# Servo-Power.net
KiCad netlist of a schematic drawn in Altium Designer
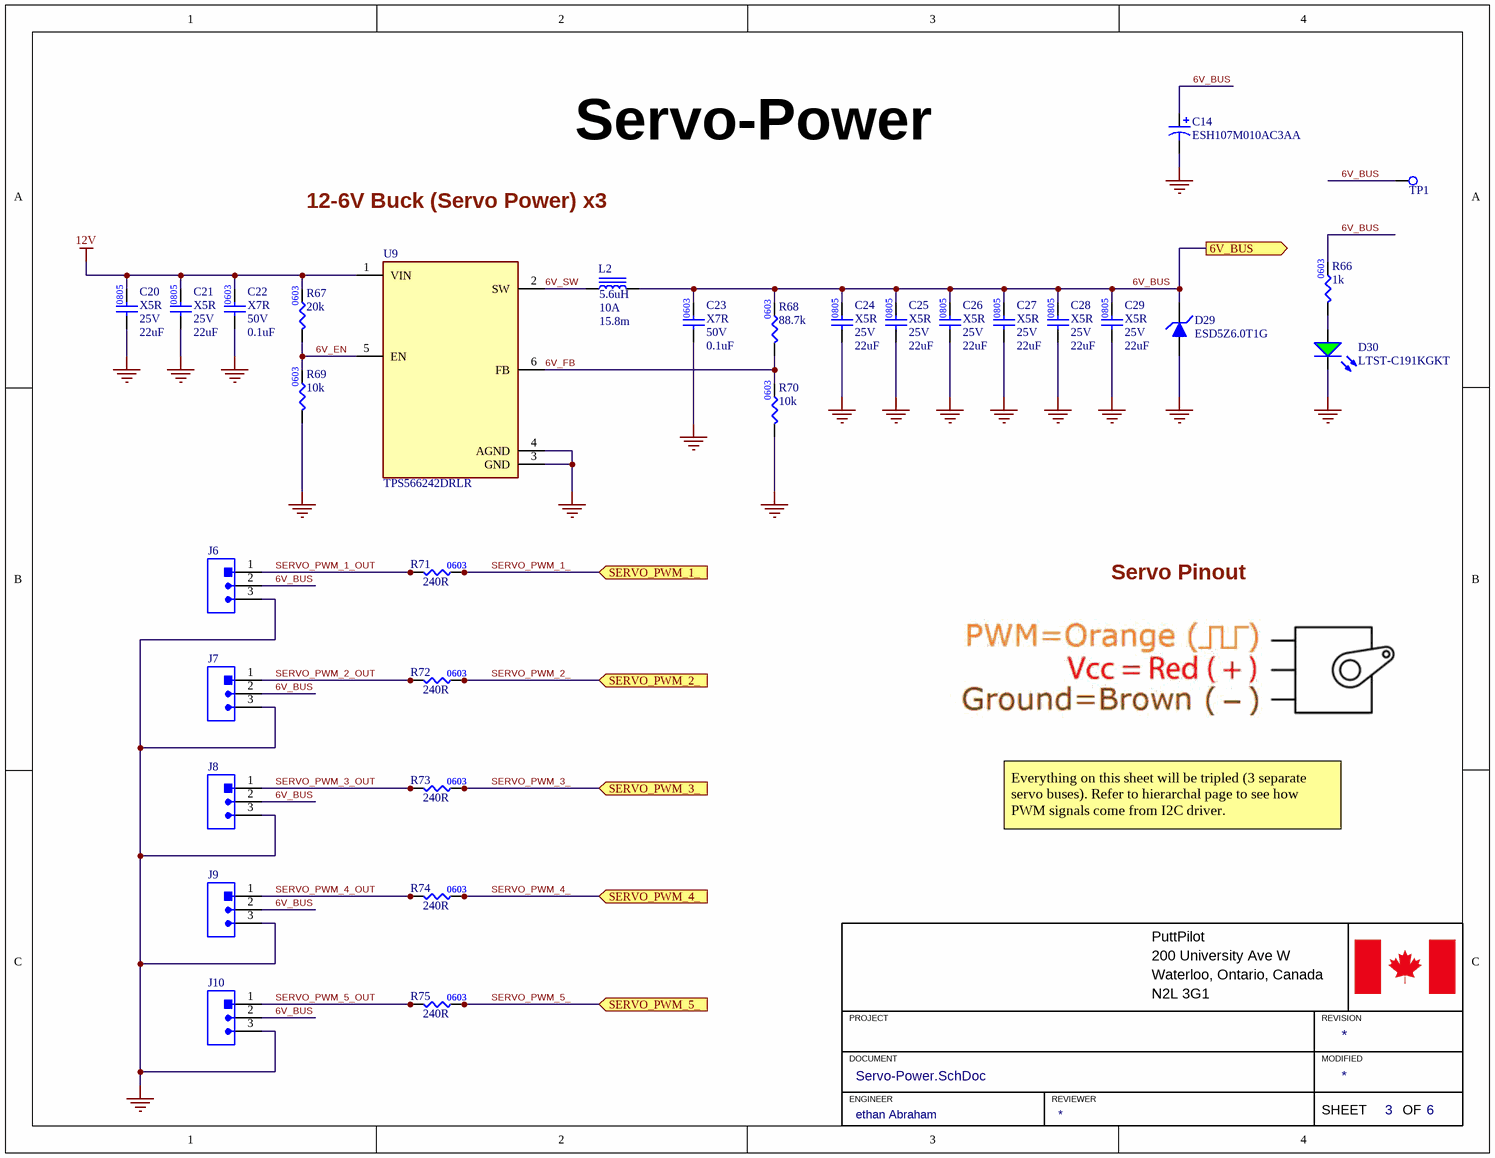
[diagram p0: Servo-Power.SchDoc]

(export (version "E")
  (design (tool "Eeschema 10.0.6"))
  (components
    (comp (ref "C14")
      (value "ESH107M010AC3AA")
      (footprint "ESH107M010AC3AA")
      (description "CAP ALUM 100uF 10V RAD THT")
      (libsource (lib "PuttPilot") (part "ESH107M010AC3AA"))
    )
    (comp (ref "C20")
      (value "GRM21BR61E226ME44K")
      (footprint ".CAP_0805")
      (description "CAP CER 22uF 25V X5R 0805")
      (fields
        (field (name "MANUFACTURER") "Murata")
        (field (name "TEMPERATURE CHARACTERISTICS CODE") "X5R")
        (field (name "RATED DC VOLTAGE (URDC)") "25V")
        (field (name "CAPACITANCE") "22uF")
      )
      (libsource (lib "PuttPilot") (part "GRM21BR61E226ME44K"))
    )
    (comp (ref "C21")
      (value "GRM21BR61E226ME44K")
      (footprint ".CAP_0805")
      (description "CAP CER 22uF 25V X5R 0805")
      (fields
        (field (name "MANUFACTURER") "Murata")
        (field (name "TEMPERATURE CHARACTERISTICS CODE") "X5R")
        (field (name "RATED DC VOLTAGE (URDC)") "25V")
        (field (name "CAPACITANCE") "22uF")
      )
      (libsource (lib "PuttPilot") (part "GRM21BR61E226ME44K"))
    )
    (comp (ref "C22")
      (value "GCJ188R71H104KA12D")
      (footprint ".CAP_0603")
      (description "CAP CER 0.1uF 50V X7R 0603")
      (fields
        (field (name "MANUFACTURER") "Murata")
        (field (name "TEMPERATURE CHARACTERISTICS CODE") "X7R")
        (field (name "RATED DC VOLTAGE (URDC)") "50V")
        (field (name "CAPACITANCE") "0.1uF")
      )
      (libsource (lib "PuttPilot") (part "GCJ188R71H104KA12D"))
    )
    (comp (ref "C23")
      (value "GCJ188R71H104KA12D")
      (footprint ".CAP_0603")
      (description "CAP CER 0.1uF 50V X7R 0603")
      (fields
        (field (name "MANUFACTURER") "Murata")
        (field (name "TEMPERATURE CHARACTERISTICS CODE") "X7R")
        (field (name "RATED DC VOLTAGE (URDC)") "50V")
        (field (name "CAPACITANCE") "0.1uF")
      )
      (libsource (lib "PuttPilot") (part "GCJ188R71H104KA12D"))
    )
    (comp (ref "C24")
      (value "GRM21BR61E226ME44K")
      (footprint ".CAP_0805")
      (description "CAP CER 22uF 25V X5R 0805")
      (fields
        (field (name "MANUFACTURER") "Murata")
        (field (name "TEMPERATURE CHARACTERISTICS CODE") "X5R")
        (field (name "RATED DC VOLTAGE (URDC)") "25V")
        (field (name "CAPACITANCE") "22uF")
      )
      (libsource (lib "PuttPilot") (part "GRM21BR61E226ME44K"))
    )
    (comp (ref "C25")
      (value "GRM21BR61E226ME44K")
      (footprint ".CAP_0805")
      (description "CAP CER 22uF 25V X5R 0805")
      (fields
        (field (name "MANUFACTURER") "Murata")
        (field (name "TEMPERATURE CHARACTERISTICS CODE") "X5R")
        (field (name "RATED DC VOLTAGE (URDC)") "25V")
        (field (name "CAPACITANCE") "22uF")
      )
      (libsource (lib "PuttPilot") (part "GRM21BR61E226ME44K"))
    )
    (comp (ref "C26")
      (value "GRM21BR61E226ME44K")
      (footprint ".CAP_0805")
      (description "CAP CER 22uF 25V X5R 0805")
      (fields
        (field (name "MANUFACTURER") "Murata")
        (field (name "TEMPERATURE CHARACTERISTICS CODE") "X5R")
        (field (name "RATED DC VOLTAGE (URDC)") "25V")
        (field (name "CAPACITANCE") "22uF")
      )
      (libsource (lib "PuttPilot") (part "GRM21BR61E226ME44K"))
    )
    (comp (ref "C27")
      (value "GRM21BR61E226ME44K")
      (footprint ".CAP_0805")
      (description "CAP CER 22uF 25V X5R 0805")
      (fields
        (field (name "MANUFACTURER") "Murata")
        (field (name "TEMPERATURE CHARACTERISTICS CODE") "X5R")
        (field (name "RATED DC VOLTAGE (URDC)") "25V")
        (field (name "CAPACITANCE") "22uF")
      )
      (libsource (lib "PuttPilot") (part "GRM21BR61E226ME44K"))
    )
    (comp (ref "C28")
      (value "GRM21BR61E226ME44K")
      (footprint ".CAP_0805")
      (description "CAP CER 22uF 25V X5R 0805")
      (fields
        (field (name "MANUFACTURER") "Murata")
        (field (name "TEMPERATURE CHARACTERISTICS CODE") "X5R")
        (field (name "RATED DC VOLTAGE (URDC)") "25V")
        (field (name "CAPACITANCE") "22uF")
      )
      (libsource (lib "PuttPilot") (part "GRM21BR61E226ME44K"))
    )
    (comp (ref "C29")
      (value "GRM21BR61E226ME44K")
      (footprint ".CAP_0805")
      (description "CAP CER 22uF 25V X5R 0805")
      (fields
        (field (name "MANUFACTURER") "Murata")
        (field (name "TEMPERATURE CHARACTERISTICS CODE") "X5R")
        (field (name "RATED DC VOLTAGE (URDC)") "25V")
        (field (name "CAPACITANCE") "22uF")
      )
      (libsource (lib "PuttPilot") (part "GRM21BR61E226ME44K"))
    )
    (comp (ref "D29")
      (value "ESD5Z6.0T1G")
      (footprint "ESD5Z6.0T1G")
      (description "DIODE TVS 6VWM")
      (fields (field (name "MANUFACTURER") "ON Semiconductor"))
      (libsource (lib "PuttPilot") (part "ESD5Z6.0T1G"))
    )
    (comp (ref "D30")
      (value "LTST-C191KGKT")
      (footprint ".LED_0603")
      (description "LED GREEN 2V 0603")
      (fields (field (name "MANUFACTURER") "Vishay Lite-On"))
      (libsource (lib "PuttPilot") (part "LTST-C191KGKT"))
    )
    (comp (ref "J6")
      (value "PRPC040SAAN-RC")
      (footprint "HEADER_3POS_2.54MM")
      (description "CONN HEADER VERT 3POS 2.54MM")
      (fields (field (name "MANUFACTURER") "Sullins"))
      (libsource (lib "PuttPilot") (part "PRPC040SAAN-RC"))
    )
    (comp (ref "J7")
      (value "PRPC040SAAN-RC")
      (footprint "HEADER_3POS_2.54MM")
      (description "CONN HEADER VERT 3POS 2.54MM")
      (fields (field (name "MANUFACTURER") "Sullins"))
      (libsource (lib "PuttPilot") (part "PRPC040SAAN-RC"))
    )
    (comp (ref "J8")
      (value "PRPC040SAAN-RC")
      (footprint "HEADER_3POS_2.54MM")
      (description "CONN HEADER VERT 3POS 2.54MM")
      (fields (field (name "MANUFACTURER") "Sullins"))
      (libsource (lib "PuttPilot") (part "PRPC040SAAN-RC"))
    )
    (comp (ref "J9")
      (value "PRPC040SAAN-RC")
      (footprint "HEADER_3POS_2.54MM")
      (description "CONN HEADER VERT 3POS 2.54MM")
      (fields (field (name "MANUFACTURER") "Sullins"))
      (libsource (lib "PuttPilot") (part "PRPC040SAAN-RC"))
    )
    (comp (ref "J10")
      (value "PRPC040SAAN-RC")
      (footprint "HEADER_3POS_2.54MM")
      (description "CONN HEADER VERT 3POS 2.54MM")
      (fields (field (name "MANUFACTURER") "Sullins"))
      (libsource (lib "PuttPilot") (part "PRPC040SAAN-RC"))
    )
    (comp (ref "L2")
      (value "SRP6060FA-5R6M")
      (footprint "SRP6060FA-5R6M")
      (description "FIXED IND 5.6uH 10A 15.8mOhm")
      (fields
        (field (name "MANUFACTURER") "Bourns")
        (field (name "INDUCTANCE") "5.6uH")
        (field (name "CURRENT RATING") "10A")
        (field (name "DC RESISTANCE") "15.8m")
      )
      (libsource (lib "PuttPilot") (part "SRP6060FA-5R6M"))
    )
    (comp (ref "R66")
      (value "RC0603FR-071KL")
      (footprint ".RES_0603")
      (description "RES 1K OHM 0603")
      (fields
        (field (name "MANUFACTURER") "Yageo")
        (field (name "TOLERANCE") "1%")
        (field (name "RESISTANCE") "1k")
      )
      (libsource (lib "PuttPilot") (part "RC0603FR-071KL"))
    )
    (comp (ref "R67")
      (value "ERJ-3EKF2002V")
      (footprint ".RES_0603")
      (description "RES 20K OHM 0603")
      (fields
        (field (name "MANUFACTURER") "Panasonic")
        (field (name "TOLERANCE") "1%")
        (field (name "RESISTANCE") "20k")
      )
      (libsource (lib "PuttPilot") (part "ERJ-3EKF2002V"))
    )
    (comp (ref "R68")
      (value "RC0603FR-0788K7L")
      (footprint ".RES_0603")
      (description "RES 88.7K OHM 0603")
      (fields
        (field (name "MANUFACTURER") "Yageo")
        (field (name "TOLERANCE") "1%")
        (field (name "RESISTANCE") "88.7k")
      )
      (libsource (lib "PuttPilot") (part "RC0603FR-0788K7L"))
    )
    (comp (ref "R69")
      (value "RC0603FR-0710KL")
      (footprint ".RES_0603")
      (description "RES 10K OHM 0603")
      (fields
        (field (name "MANUFACTURER") "Yageo")
        (field (name "TOLERANCE") "1%")
        (field (name "RESISTANCE") "10k")
      )
      (libsource (lib "PuttPilot") (part "RC0603FR-0710KL"))
    )
    (comp (ref "R70")
      (value "RC0603FR-0710KL")
      (footprint ".RES_0603")
      (description "RES 10K OHM 0603")
      (fields
        (field (name "MANUFACTURER") "Yageo")
        (field (name "TOLERANCE") "1%")
        (field (name "RESISTANCE") "10k")
      )
      (libsource (lib "PuttPilot") (part "RC0603FR-0710KL"))
    )
    (comp (ref "R71")
      (value "RC0603FR-07240RL")
      (footprint ".RES_0603")
      (description "RES 240 OHM 0603")
      (fields
        (field (name "MANUFACTURER") "Yageo")
        (field (name "TOLERANCE") "1%")
        (field (name "RESISTANCE") "240R")
      )
      (libsource (lib "PuttPilot") (part "RC0603FR-07240RL"))
    )
    (comp (ref "R72")
      (value "RC0603FR-07240RL")
      (footprint ".RES_0603")
      (description "RES 240 OHM 0603")
      (fields
        (field (name "MANUFACTURER") "Yageo")
        (field (name "TOLERANCE") "1%")
        (field (name "RESISTANCE") "240R")
      )
      (libsource (lib "PuttPilot") (part "RC0603FR-07240RL"))
    )
    (comp (ref "R73")
      (value "RC0603FR-07240RL")
      (footprint ".RES_0603")
      (description "RES 240 OHM 0603")
      (fields
        (field (name "MANUFACTURER") "Yageo")
        (field (name "TOLERANCE") "1%")
        (field (name "RESISTANCE") "240R")
      )
      (libsource (lib "PuttPilot") (part "RC0603FR-07240RL"))
    )
    (comp (ref "R74")
      (value "RC0603FR-07240RL")
      (footprint ".RES_0603")
      (description "RES 240 OHM 0603")
      (fields
        (field (name "MANUFACTURER") "Yageo")
        (field (name "TOLERANCE") "1%")
        (field (name "RESISTANCE") "240R")
      )
      (libsource (lib "PuttPilot") (part "RC0603FR-07240RL"))
    )
    (comp (ref "R75")
      (value "RC0603FR-07240RL")
      (footprint ".RES_0603")
      (description "RES 240 OHM 0603")
      (fields
        (field (name "MANUFACTURER") "Yageo")
        (field (name "TOLERANCE") "1%")
        (field (name "RESISTANCE") "240R")
      )
      (libsource (lib "PuttPilot") (part "RC0603FR-07240RL"))
    )
    (comp (ref "TP1")
      (value "RCWCTE")
      (footprint "RCWCTE")
      (description "SMT Test Point")
      (fields (field (name "MANUFACTURER") "KOA Speer"))
      (libsource (lib "PuttPilot") (part "RCWCTE"))
    )
    (comp (ref "U9")
      (value "TPS566242DRLR")
      (footprint "TPS566242DRLR")
      (description "BUCK 3V-16V 6A SOT-563")
      (fields (field (name "MANUFACTURER") "Texas Instruments"))
      (libsource (lib "PuttPilot") (part "TPS566242DRLR"))
    )
  )
  (nets
    (net (code "1") (name "/6V_BUS") (class "Default")
      (node (ref "C14") (pin "1") (pinfunction "1_1") (pintype "passive"))
      (node (ref "C23") (pin "2") (pinfunction "2_2") (pintype "passive"))
      (node (ref "C24") (pin "2") (pinfunction "2_2") (pintype "passive"))
      (node (ref "C25") (pin "2") (pinfunction "2_2") (pintype "passive"))
      (node (ref "C26") (pin "2") (pinfunction "2_2") (pintype "passive"))
      (node (ref "C27") (pin "2") (pinfunction "2_2") (pintype "passive"))
      (node (ref "C28") (pin "2") (pinfunction "2_2") (pintype "passive"))
      (node (ref "C29") (pin "2") (pinfunction "2_2") (pintype "passive"))
      (node (ref "D29") (pin "1") (pinfunction "Cathode_1") (pintype "passive"))
      (node (ref "J10") (pin "2") (pinfunction "2_2") (pintype "passive"))
      (node (ref "J6") (pin "2") (pinfunction "2_2") (pintype "passive"))
      (node (ref "J7") (pin "2") (pinfunction "2_2") (pintype "passive"))
      (node (ref "J8") (pin "2") (pinfunction "2_2") (pintype "passive"))
      (node (ref "J9") (pin "2") (pinfunction "2_2") (pintype "passive"))
      (node (ref "L2") (pin "2") (pinfunction "2_2") (pintype "passive"))
      (node (ref "R66") (pin "2") (pinfunction "2_2") (pintype "passive"))
      (node (ref "R68") (pin "2") (pinfunction "2_2") (pintype "passive"))
      (node (ref "TP1") (pin "1") (pinfunction "1_1") (pintype "passive"))
    )
    (net (code "2") (name "/6V_EN") (class "Default")
      (node (ref "R67") (pin "1") (pinfunction "1_1") (pintype "passive"))
      (node (ref "R69") (pin "2") (pinfunction "2_2") (pintype "passive"))
      (node (ref "U9") (pin "5") (pinfunction "EN_5") (pintype "passive"))
    )
    (net (code "3") (name "/6V_FB") (class "Default")
      (node (ref "R68") (pin "1") (pinfunction "1_1") (pintype "passive"))
      (node (ref "R70") (pin "2") (pinfunction "2_2") (pintype "passive"))
      (node (ref "U9") (pin "6") (pinfunction "FB_6") (pintype "passive"))
    )
    (net (code "4") (name "/6V_SW") (class "Default")
      (node (ref "L2") (pin "1") (pinfunction "1_1") (pintype "passive"))
      (node (ref "U9") (pin "2") (pinfunction "SW_2") (pintype "passive"))
    )
    (net (code "5") (name "/SERVO_PWM_1_") (class "Default")
      (node (ref "R71") (pin "2") (pinfunction "2_2") (pintype "passive"))
    )
    (net (code "6") (name "/SERVO_PWM_1_OUT") (class "Default")
      (node (ref "J6") (pin "1") (pinfunction "1_1") (pintype "passive"))
      (node (ref "R71") (pin "1") (pinfunction "1_1") (pintype "passive"))
    )
    (net (code "7") (name "/SERVO_PWM_2_") (class "Default")
      (node (ref "R72") (pin "2") (pinfunction "2_2") (pintype "passive"))
    )
    (net (code "8") (name "/SERVO_PWM_2_OUT") (class "Default")
      (node (ref "J7") (pin "1") (pinfunction "1_1") (pintype "passive"))
      (node (ref "R72") (pin "1") (pinfunction "1_1") (pintype "passive"))
    )
    (net (code "9") (name "/SERVO_PWM_3_") (class "Default")
      (node (ref "R73") (pin "2") (pinfunction "2_2") (pintype "passive"))
    )
    (net (code "10") (name "/SERVO_PWM_3_OUT") (class "Default")
      (node (ref "J8") (pin "1") (pinfunction "1_1") (pintype "passive"))
      (node (ref "R73") (pin "1") (pinfunction "1_1") (pintype "passive"))
    )
    (net (code "11") (name "/SERVO_PWM_4_") (class "Default")
      (node (ref "R74") (pin "2") (pinfunction "2_2") (pintype "passive"))
    )
    (net (code "12") (name "/SERVO_PWM_4_OUT") (class "Default")
      (node (ref "J9") (pin "1") (pinfunction "1_1") (pintype "passive"))
      (node (ref "R74") (pin "1") (pinfunction "1_1") (pintype "passive"))
    )
    (net (code "13") (name "/SERVO_PWM_5_") (class "Default")
      (node (ref "R75") (pin "2") (pinfunction "2_2") (pintype "passive"))
    )
    (net (code "14") (name "/SERVO_PWM_5_OUT") (class "Default")
      (node (ref "J10") (pin "1") (pinfunction "1_1") (pintype "passive"))
      (node (ref "R75") (pin "1") (pinfunction "1_1") (pintype "passive"))
    )
    (net (code "15") (name "12V") (class "Default")
      (node (ref "C20") (pin "2") (pinfunction "2_2") (pintype "passive"))
      (node (ref "C21") (pin "2") (pinfunction "2_2") (pintype "passive"))
      (node (ref "C22") (pin "2") (pinfunction "2_2") (pintype "passive"))
      (node (ref "R67") (pin "2") (pinfunction "2_2") (pintype "passive"))
      (node (ref "U9") (pin "1") (pinfunction "VIN_1") (pintype "passive"))
    )
    (net (code "16") (name "GND") (class "Default")
      (node (ref "C14") (pin "2") (pinfunction "2_2") (pintype "passive"))
      (node (ref "C20") (pin "1") (pinfunction "1_1") (pintype "passive"))
      (node (ref "C21") (pin "1") (pinfunction "1_1") (pintype "passive"))
      (node (ref "C22") (pin "1") (pinfunction "1_1") (pintype "passive"))
      (node (ref "C23") (pin "1") (pinfunction "1_1") (pintype "passive"))
      (node (ref "C24") (pin "1") (pinfunction "1_1") (pintype "passive"))
      (node (ref "C25") (pin "1") (pinfunction "1_1") (pintype "passive"))
      (node (ref "C26") (pin "1") (pinfunction "1_1") (pintype "passive"))
      (node (ref "C27") (pin "1") (pinfunction "1_1") (pintype "passive"))
      (node (ref "C28") (pin "1") (pinfunction "1_1") (pintype "passive"))
      (node (ref "C29") (pin "1") (pinfunction "1_1") (pintype "passive"))
      (node (ref "D29") (pin "2") (pinfunction "Anode_2") (pintype "passive"))
      (node (ref "D30") (pin "2") (pinfunction "K_2") (pintype "passive"))
      (node (ref "J10") (pin "3") (pinfunction "3_3") (pintype "passive"))
      (node (ref "J6") (pin "3") (pinfunction "3_3") (pintype "passive"))
      (node (ref "J7") (pin "3") (pinfunction "3_3") (pintype "passive"))
      (node (ref "J8") (pin "3") (pinfunction "3_3") (pintype "passive"))
      (node (ref "J9") (pin "3") (pinfunction "3_3") (pintype "passive"))
      (node (ref "R69") (pin "1") (pinfunction "1_1") (pintype "passive"))
      (node (ref "R70") (pin "1") (pinfunction "1_1") (pintype "passive"))
      (node (ref "U9") (pin "3") (pinfunction "GND_3") (pintype "passive"))
      (node (ref "U9") (pin "4") (pinfunction "AGND_4") (pintype "passive"))
    )
    (net (code "17") (name "Net-(D30-A)") (class "Default")
      (node (ref "D30") (pin "1") (pinfunction "A_1") (pintype "passive"))
      (node (ref "R66") (pin "1") (pinfunction "1_1") (pintype "passive"))
    )
  )
)
